# Sch_pwr.net
KiCad netlist of a schematic drawn in Altium Designer
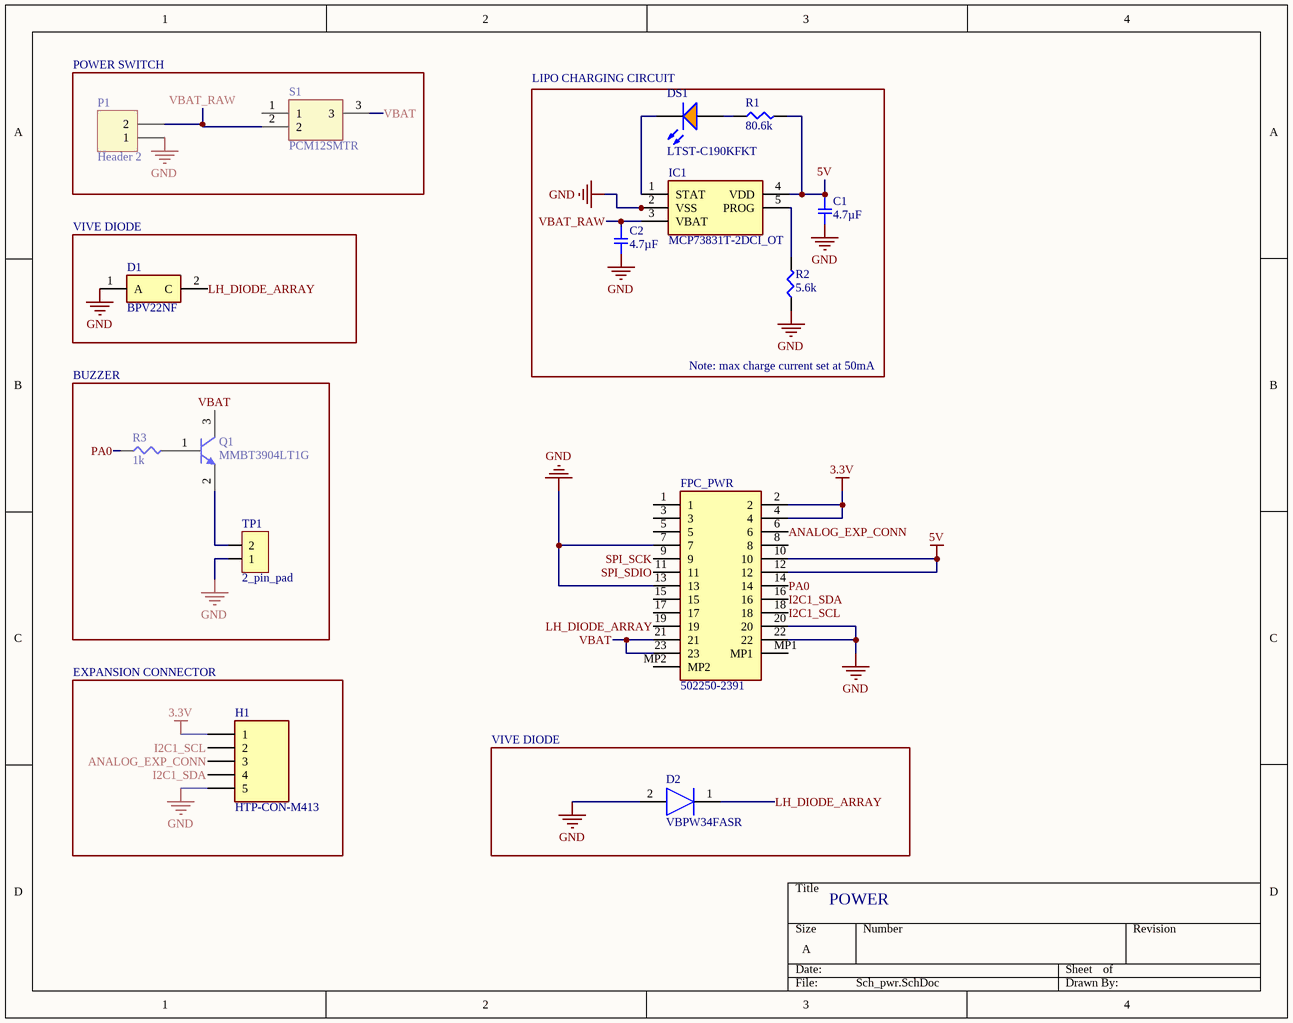
[diagram p0: Sch_pwr.SchDoc]

(export (version "E")
  (design (tool "Eeschema 10.0.6"))
  (components
    (comp (ref "C1")
      (value "4.7µF")
      (footprint "SMD-0402C")
      (description "CAP CER 4.7UF 4V X5R 0402")
      (fields
        (field (name "DIGI-KEY PART NUMBER") "490-13231-1-ND")
        (field (name "PART NUMBER") "GRM153R60G475ME15D")
      )
      (libsource (lib "capacitor_murata_0402") (part "GRM153R60G475ME15D"))
    )
    (comp (ref "C2")
      (value "4.7µF")
      (footprint "SMD-0402C")
      (description "CAP CER 4.7UF 4V X5R 0402")
      (fields
        (field (name "DIGI-KEY PART NUMBER") "490-13231-1-ND")
        (field (name "PART NUMBER") "GRM153R60G475ME15D")
      )
      (libsource (lib "capacitor_murata_0402") (part "GRM153R60G475ME15D"))
    )
    (comp (ref "D1")
      (value "BPV22NF")
      (footprint "SamacSys:TO254P510X450X920-2P")
      (description "Diode")
      (fields (field (name "MOUSER PART NUMBER") "782-BPV22NF") (field (name "RS PART NUMBER") "6997604P"))
      (libsource (lib "*") (part "BPV22NF"))
    )
    (comp (ref "D2")
      (value "VBPW34FASR")
      (footprint "VBPW34FASR")
      (description "Diode")
      (fields (field (name "MOUSER PART NUMBER") "782-VBPW34FASR") (field (name "RS PART NUMBER") "7689401"))
      (libsource (lib "*") (part "VBPW34FASR"))
    )
    (comp (ref "DS1")
      (value "LTST-C190KFKT")
      (footprint "LTST-C190KFKT_V")
      (description "LED Uni-Color Orange, 75 mW, 30 mA, -35 to 85 degC, 2-Pin SMD, RoHS, Tape and Reel")
      (fields (field (name "TOLERANCE") "1%"))
      (libsource (lib "Altium Content Vault") (part "LED-ORANGE-AK-2"))
    )
    (comp (ref "FPC_PWR")
      (value "502250-2391")
      (footprint "SamacSys:5022502391")
      (description "Connector")
      (fields (field (name "MOUSER PART NUMBER") "538-502250-2391"))
      (libsource (lib "*") (part "502250-2391"))
    )
    (comp (ref "H1")
      (value "HTP-CON-M413")
      (footprint "SamacSys:HTP-CON-M413")
      (libsource (lib "SamacSys") (part "HTP-CON-M413"))
    )
    (comp (ref "IC1")
      (value "MCP73831T-2DCI_OT")
      (footprint "SamacSys:SOT95P270X145-5N")
      (description "Integrated Circuit")
      (fields
        (field (name "MANUFACTURER_PART_NUMBER") "MCP73831T-2DCI/OT")
        (field (name "MOUSER PART NUMBER") "579-MCP73831T-2DCIOT")
      )
      (libsource (lib "*") (part "MCP73831T-2DCI_OT"))
    )
    (comp (ref "P1")
      (value "Header 2")
      (footprint "HDR1X2")
      (description "Header, 2-Pin")
      (fields (field (name "PUBLISHER") "Altium Limited"))
      (libsource (lib "Miscellaneous Connectors") (part "Header 2"))
    )
    (comp (ref "Q1")
      (value "MMBT3904LT1G")
      (footprint "ONSC-SOT-23-3-318-08_V")
      (description "General Purpose Transistor, NPN Silicon, 3-Pin SOT-23, Pb-Free, Tape and Reel")
      (fields (field (name "MANUFACTURER") "On Semiconductor"))
      (libsource (lib "Altium Content Vault") (part "ONSC-NPN-B1E2C3-3"))
    )
    (comp (ref "R1")
      (value "80.6k")
      (footprint "SMD-0402-RES")
      (description "RES SMD 80.6K OHM 1% 1/10W 0402")
      (fields
        (field (name "PART NUMBER") "ERJ-2RKF8062X")
        (field (name "DIGI-KEY PART NUMBER") "P80.6KLCT-ND")
      )
      (libsource (lib "Panasonic_ERJ_0402") (part "ERJ-2RKF8062X"))
    )
    (comp (ref "R2")
      (value "5.6k")
      (footprint "SMD-0402-RES")
      (description "RES SMD 5.6K OHM 5% 1/10W 0402")
      (fields (field (name "PART NUMBER") "ERJ-2GEJ562X") (field (name "DIGI-KEY PART NUMBER") "P5.6KJCT-ND"))
      (libsource (lib "Panasonic_ERJ_0402") (part "ERJ-2GEJ562X"))
    )
    (comp (ref "R3")
      (value "1k")
      (footprint "SMD-0402-RES")
      (description "RES SMD 1K OHM 5% 1/10W 0402")
      (fields (field (name "PART NUMBER") "ERJ-2GEJ102X") (field (name "DIGI-KEY PART NUMBER") "P1.0KJCT-ND"))
      (libsource (lib "Panasonic_ERJ_0402") (part "ERJ-2GEJ102X"))
    )
    (comp (ref "S1")
      (value "PCM12SMTR")
      (footprint "SamacSys:PCM12SMTR_1")
      (description "Switch")
      (fields (field (name "MOUSER PART NUMBER") "611-PCM12SMTR") (field (name "RS PART NUMBER") "7931721P"))
      (libsource (lib "*") (part "PCM12SMTR"))
    )
    (comp (ref "TP1")
      (value "2_pin_pad")
      (footprint "Edge Connector (2-mini)")
      (libsource (lib "schematic_components") (part "2_pin_pad"))
    )
  )
  (nets
    (net (code "2") (name "/ANALOG_EXP_CONN") (class "Default")
      (node (ref "FPC_PWR") (pin "6") (pinfunction "6_6") (pintype "passive"))
      (node (ref "H1") (pin "3") (pinfunction "3_3") (pintype "passive"))
    )
    (net (code "3") (name "/I2C1_SCL") (class "Default")
      (node (ref "FPC_PWR") (pin "18") (pinfunction "18_18") (pintype "passive"))
      (node (ref "H1") (pin "2") (pinfunction "2_2") (pintype "passive"))
    )
    (net (code "4") (name "/I2C1_SDA") (class "Default")
      (node (ref "FPC_PWR") (pin "16") (pinfunction "16_16") (pintype "passive"))
      (node (ref "H1") (pin "4") (pinfunction "4_4") (pintype "passive"))
    )
    (net (code "5") (name "/LH_DIODE_ARRAY") (class "Default")
      (node (ref "D1") (pin "2") (pinfunction "C_2") (pintype "passive"))
      (node (ref "D2") (pin "1") (pinfunction "A_1") (pintype "passive"))
      (node (ref "FPC_PWR") (pin "19") (pinfunction "19_19") (pintype "passive"))
    )
    (net (code "6") (name "/PA0") (class "Default")
      (node (ref "FPC_PWR") (pin "14") (pinfunction "14_14") (pintype "passive"))
      (node (ref "R3") (pin "1") (pinfunction "1_1") (pintype "passive"))
    )
    (net (code "7") (name "/SPI_SCK") (class "Default")
      (node (ref "FPC_PWR") (pin "9") (pinfunction "9_9") (pintype "passive"))
    )
    (net (code "8") (name "/SPI_SDIO") (class "Default")
      (node (ref "FPC_PWR") (pin "11") (pinfunction "11_11") (pintype "passive"))
    )
    (net (code "9") (name "/VBAT") (class "Default")
      (node (ref "FPC_PWR") (pin "21") (pinfunction "21_21") (pintype "passive"))
      (node (ref "FPC_PWR") (pin "23") (pinfunction "23_23") (pintype "passive"))
      (node (ref "Q1") (pin "3") (pinfunction "C_3") (pintype "passive"))
      (node (ref "S1") (pin "3") (pinfunction "3_3") (pintype "passive"))
    )
    (net (code "10") (name "/VBAT_RAW") (class "Default")
      (node (ref "C2") (pin "1") (pinfunction "1_1") (pintype "passive"))
      (node (ref "IC1") (pin "3") (pinfunction "VBAT_3") (pintype "passive"))
      (node (ref "P1") (pin "2") (pinfunction "2_2") (pintype "passive"))
      (node (ref "S1") (pin "2") (pinfunction "2_2") (pintype "passive"))
    )
    (net (code "11") (name "3.3V") (class "Default")
      (node (ref "FPC_PWR") (pin "2") (pinfunction "2_2") (pintype "passive"))
      (node (ref "FPC_PWR") (pin "4") (pinfunction "4_4") (pintype "passive"))
      (node (ref "H1") (pin "1") (pinfunction "1_1") (pintype "passive"))
    )
    (net (code "12") (name "5V") (class "Default")
      (node (ref "C1") (pin "1") (pinfunction "1_1") (pintype "passive"))
      (node (ref "FPC_PWR") (pin "10") (pinfunction "10_10") (pintype "passive"))
      (node (ref "FPC_PWR") (pin "12") (pinfunction "12_12") (pintype "passive"))
      (node (ref "IC1") (pin "4") (pinfunction "VDD_4") (pintype "power_in"))
      (node (ref "R1") (pin "2") (pinfunction "2_2") (pintype "passive"))
    )
    (net (code "13") (name "GND") (class "Default")
      (node (ref "C1") (pin "2") (pinfunction "2_2") (pintype "passive"))
      (node (ref "C2") (pin "2") (pinfunction "2_2") (pintype "passive"))
      (node (ref "D1") (pin "1") (pinfunction "A_1") (pintype "passive"))
      (node (ref "D2") (pin "2") (pinfunction "K_2") (pintype "passive"))
      (node (ref "FPC_PWR") (pin "13") (pinfunction "13_13") (pintype "passive"))
      (node (ref "FPC_PWR") (pin "20") (pinfunction "20_20") (pintype "passive"))
      (node (ref "FPC_PWR") (pin "22") (pinfunction "22_22") (pintype "passive"))
      (node (ref "FPC_PWR") (pin "7") (pinfunction "7_7") (pintype "passive"))
      (node (ref "H1") (pin "5") (pinfunction "5_5") (pintype "passive"))
      (node (ref "IC1") (pin "2") (pinfunction "VSS_2") (pintype "power_in"))
      (node (ref "P1") (pin "1") (pinfunction "1_1") (pintype "passive"))
      (node (ref "R2") (pin "1") (pinfunction "1_1") (pintype "passive"))
      (node (ref "TP1") (pin "1") (pinfunction "1_1") (pintype "passive"))
    )
    (net (code "14") (name "Net-(DS1-A)") (class "Default")
      (node (ref "DS1") (pin "1") (pinfunction "A_1") (pintype "passive"))
      (node (ref "R1") (pin "1") (pinfunction "1_1") (pintype "passive"))
    )
    (net (code "15") (name "Net-(DS1-K)") (class "Default")
      (node (ref "DS1") (pin "2") (pinfunction "K_2") (pintype "passive"))
      (node (ref "IC1") (pin "1") (pinfunction "STAT_1") (pintype "passive"))
    )
    (net (code "16") (name "Net-(IC1-PROG)") (class "Default")
      (node (ref "IC1") (pin "5") (pinfunction "PROG_5") (pintype "passive"))
      (node (ref "R2") (pin "2") (pinfunction "2_2") (pintype "passive"))
    )
    (net (code "17") (name "Net-(Q1-B)") (class "Default")
      (node (ref "Q1") (pin "1") (pinfunction "B_1") (pintype "passive"))
      (node (ref "R3") (pin "2") (pinfunction "2_2") (pintype "passive"))
    )
    (net (code "18") (name "Net-(Q1-E)") (class "Default")
      (node (ref "Q1") (pin "2") (pinfunction "E_2") (pintype "passive"))
      (node (ref "TP1") (pin "2") (pinfunction "2_2") (pintype "passive"))
    )
    (net (code "19") (name "unconnected-(FPC_PWR-Pad1)") (class "Default")
      (node (ref "FPC_PWR") (pin "1") (pinfunction "1_1") (pintype "passive"))
    )
    (net (code "20") (name "unconnected-(FPC_PWR-Pad3)") (class "Default")
      (node (ref "FPC_PWR") (pin "3") (pinfunction "3_3") (pintype "passive"))
    )
    (net (code "21") (name "unconnected-(FPC_PWR-Pad5)") (class "Default")
      (node (ref "FPC_PWR") (pin "5") (pinfunction "5_5") (pintype "passive"))
    )
    (net (code "22") (name "unconnected-(FPC_PWR-Pad8)") (class "Default")
      (node (ref "FPC_PWR") (pin "8") (pinfunction "8_8") (pintype "passive"))
    )
    (net (code "23") (name "unconnected-(FPC_PWR-Pad15)") (class "Default")
      (node (ref "FPC_PWR") (pin "15") (pinfunction "15_15") (pintype "passive"))
    )
    (net (code "24") (name "unconnected-(FPC_PWR-Pad17)") (class "Default")
      (node (ref "FPC_PWR") (pin "17") (pinfunction "17_17") (pintype "passive"))
    )
    (net (code "25") (name "unconnected-(FPC_PWR-PadMP1)") (class "Default")
      (node (ref "FPC_PWR") (pin "MP1") (pinfunction "MP1_MP1") (pintype "passive"))
    )
    (net (code "26") (name "unconnected-(FPC_PWR-PadMP2)") (class "Default")
      (node (ref "FPC_PWR") (pin "MP2") (pinfunction "MP2_MP2") (pintype "passive"))
    )
    (net (code "27") (name "unconnected-(S1-Pad1)") (class "Default")
      (node (ref "S1") (pin "1") (pinfunction "1_1") (pintype "passive"))
    )
  )
)
